# medulla_2026-05-01.net
KiCad netlist of a schematic drawn in EasyEDA Pro
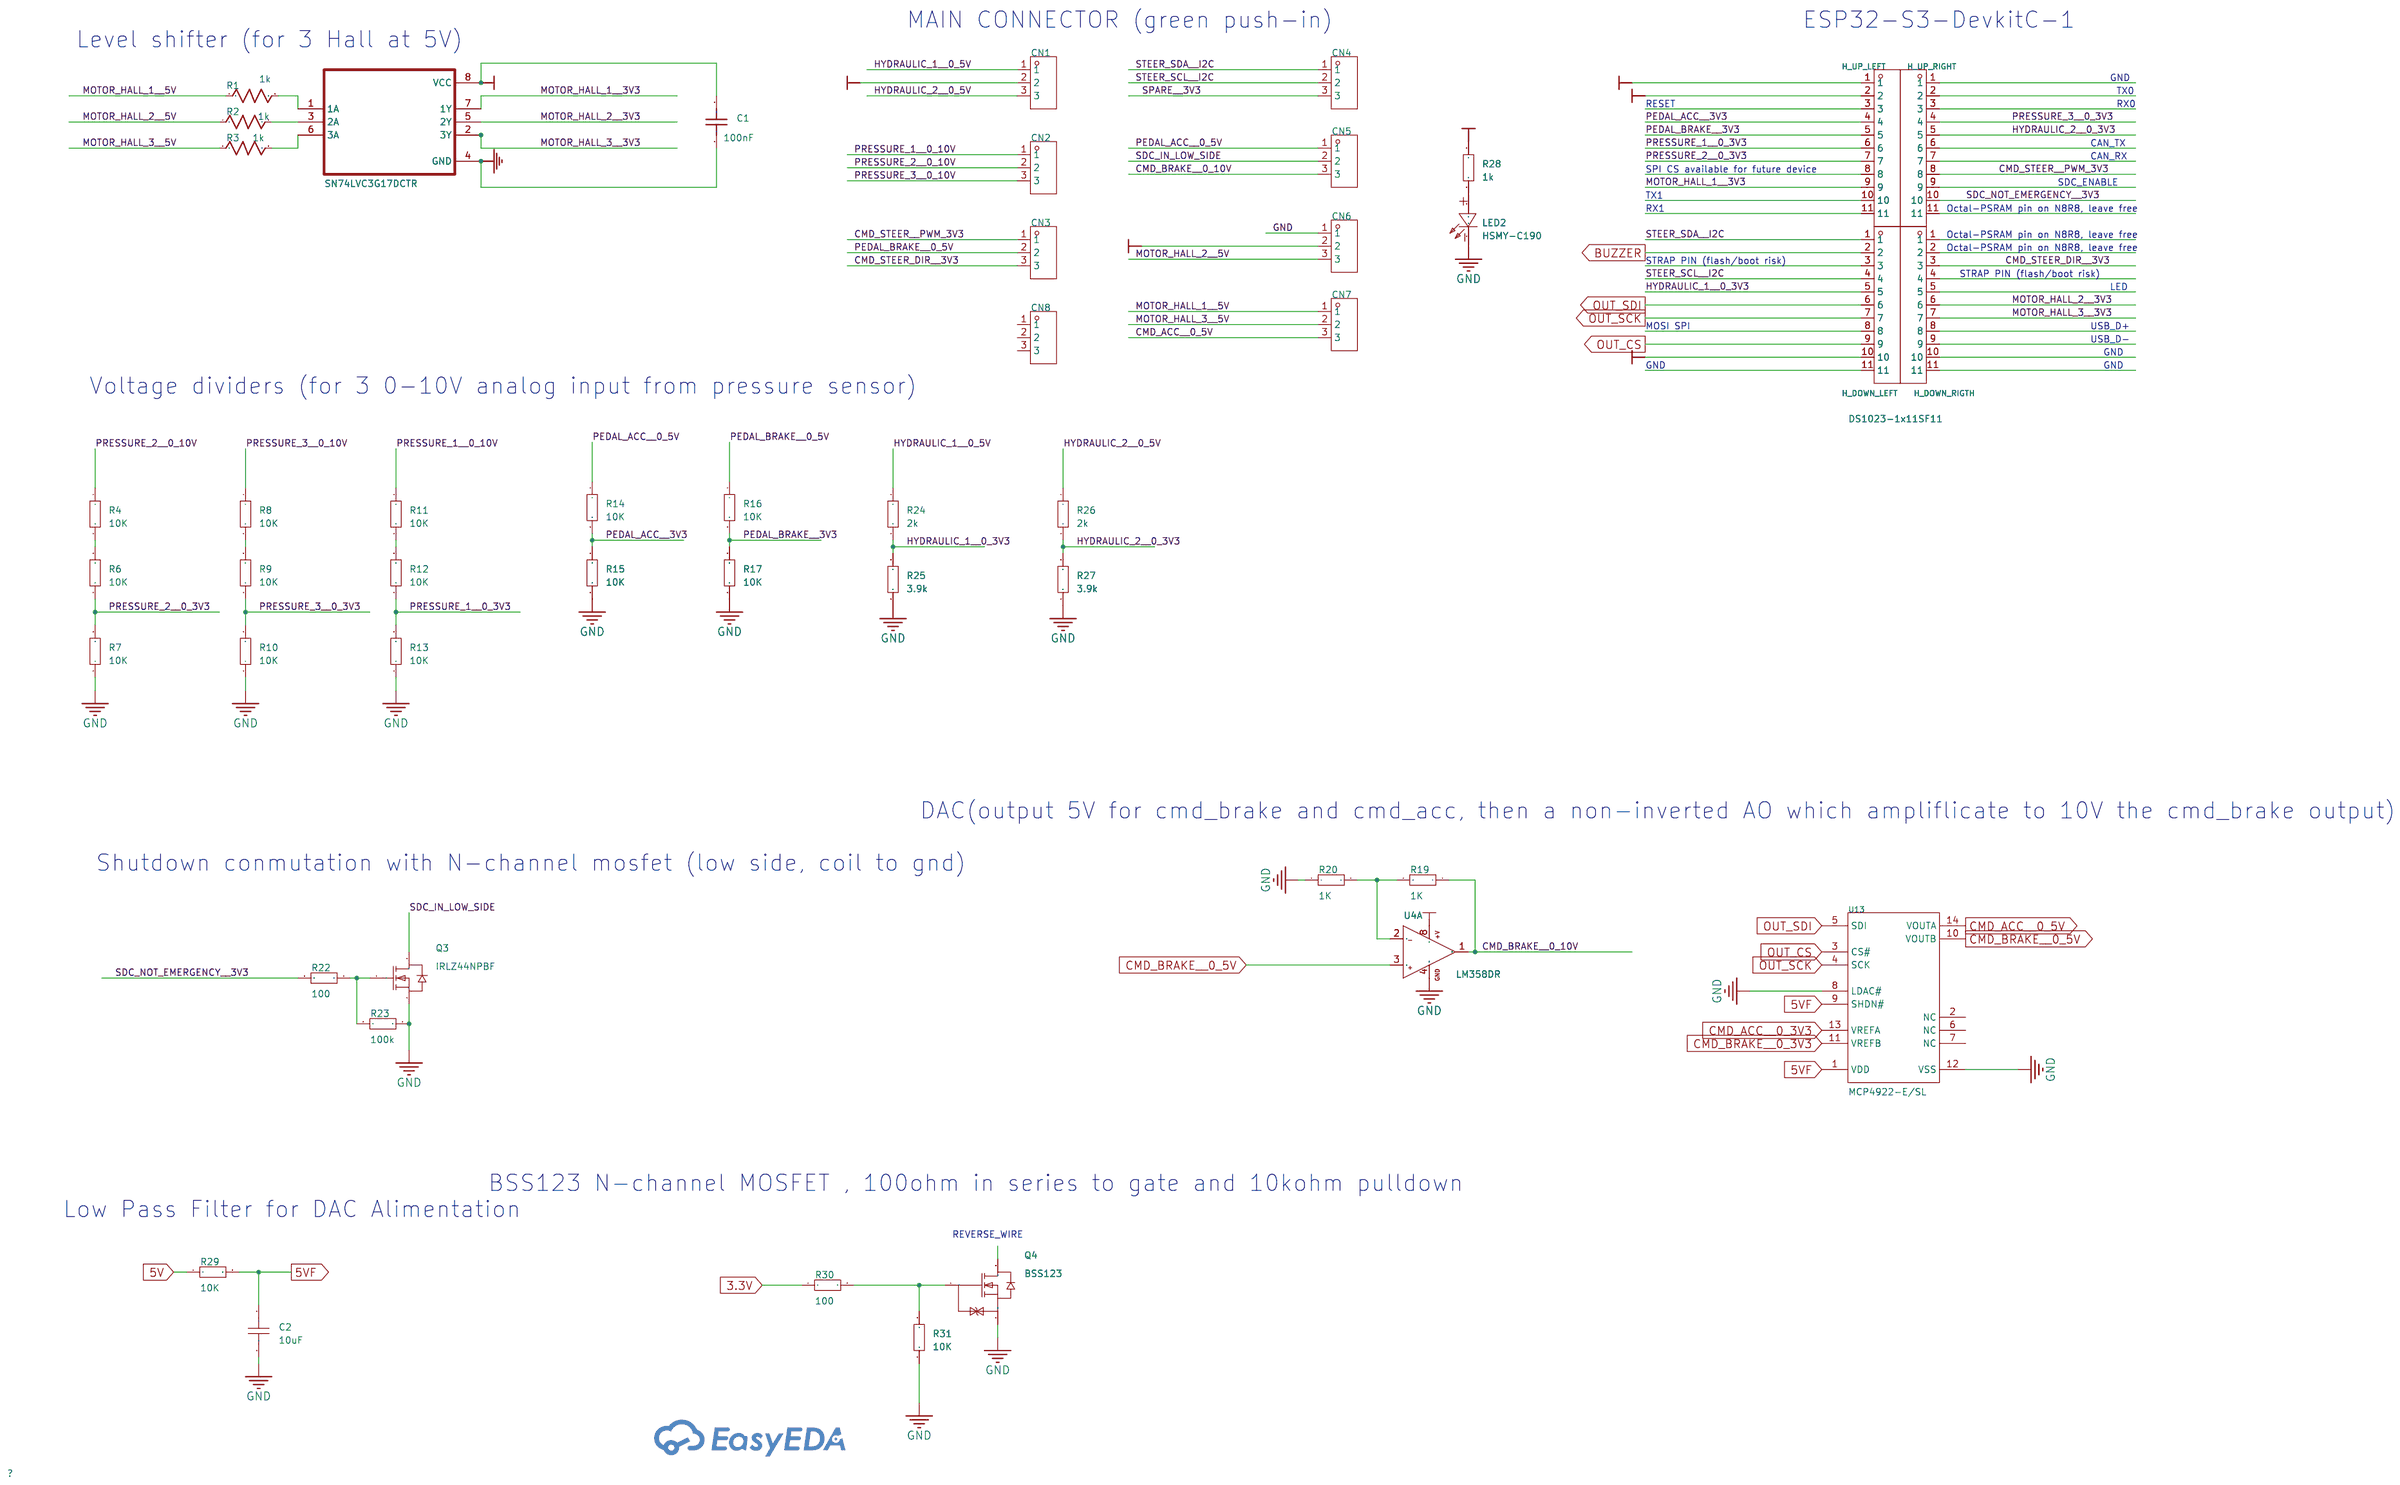
[diagram p0: schematic sheet]

(export (version "E")
  (design (tool "Eeschema 10.0.6"))
  (components
    (comp (ref "C1")
      (value "100nF")
      (footprint "easyedapro:C0603")
      (fields (field (name "Contributor") "LCEDA_Lib"))
      (libsource (lib "easyedapro") (part "100nF"))
    )
    (comp (ref "C2")
      (value "10uF")
      (footprint "easyedapro:C0603")
      (libsource (lib "easyedapro") (part "CAP"))
    )
    (comp (ref "CN1")
      (value "1990012")
      (footprint "easyedapro:CONN-TH_3P-P2.50-S5.00_1990012")
      (libsource (lib "easyedapro") (part "1990012"))
    )
    (comp (ref "CN2")
      (value "1990012")
      (footprint "easyedapro:CONN-TH_3P-P2.50-S5.00_1990012")
      (libsource (lib "easyedapro") (part "1990012"))
    )
    (comp (ref "CN3")
      (value "1990012")
      (footprint "easyedapro:CONN-TH_3P-P2.50-S5.00_1990012")
      (libsource (lib "easyedapro") (part "1990012"))
    )
    (comp (ref "CN4")
      (value "1990012")
      (footprint "easyedapro:CONN-TH_3P-P2.50-S5.00_1990012")
      (libsource (lib "easyedapro") (part "1990012"))
    )
    (comp (ref "CN5")
      (value "1990012")
      (footprint "easyedapro:CONN-TH_3P-P2.50-S5.00_1990012")
      (libsource (lib "easyedapro") (part "1990012"))
    )
    (comp (ref "CN6")
      (value "1990012")
      (footprint "easyedapro:CONN-TH_3P-P2.50-S5.00_1990012")
      (libsource (lib "easyedapro") (part "1990012"))
    )
    (comp (ref "CN7")
      (value "1990012")
      (footprint "easyedapro:CONN-TH_3P-P2.50-S5.00_1990012")
      (libsource (lib "easyedapro") (part "1990012"))
    )
    (comp (ref "CN8")
      (value "1990012")
      (footprint "easyedapro:CONN-TH_3P-P2.50-S5.00_1990012")
      (libsource (lib "easyedapro") (part "1990012"))
    )
    (comp (ref "H_DOWN_LEFT")
      (value "DS1023-1x11SF11")
      (footprint "easyedapro:HDR-TH_11P-P2.54-V-F")
      (fields (field (name "Manufacturer") "CONNFLY"))
      (libsource (lib "easyedapro") (part "DS1023-1X11SF11"))
    )
    (comp (ref "H_DOWN_RIGTH")
      (value "DS1023-1x11SF11")
      (footprint "easyedapro:HDR-TH_11P-P2.54-V-F")
      (fields (field (name "Manufacturer") "CONNFLY"))
      (libsource (lib "easyedapro") (part "DS1023-1X11SF11"))
    )
    (comp (ref "H_UP_LEFT")
      (value "DS1023-1x11SF11")
      (footprint "easyedapro:HDR-TH_11P-P2.54-V-F")
      (fields (field (name "Manufacturer") "CONNFLY"))
      (libsource (lib "easyedapro") (part "DS1023-1X11SF11"))
    )
    (comp (ref "H_UP_RIGHT")
      (value "DS1023-1x11SF11")
      (footprint "easyedapro:HDR-TH_11P-P2.54-V-F")
      (fields (field (name "Manufacturer") "CONNFLY"))
      (libsource (lib "easyedapro") (part "DS1023-1X11SF11"))
    )
    (comp (ref "LED2")
      (value "HSMY-C190")
      (footprint "easyedapro:LED-SMD_L1.6-W0.8-RD-YELLOW")
      (fields (field (name "Manufacturer") "Broadcom(博通)"))
      (libsource (lib "easyedapro") (part "HSMY-C190"))
    )
    (comp (ref "Q3")
      (value "IRLZ44NPBF")
      (footprint "easyedapro:TO-220-3_L10.0-W4.5-P2.54-T")
      (fields (field (name "Manufacturer") "Infineon(英飞凌)"))
      (libsource (lib "easyedapro") (part "IRLZ44NPBF"))
    )
    (comp (ref "Q4")
      (value "BSS123")
      (footprint "easyedapro:SOT-23_L2.9-W1.3-P1.90-LS2.4-BR")
      (fields (field (name "Manufacturer") "HXY MOSFET(华轩阳电子)"))
      (libsource (lib "easyedapro") (part "BSS123_C5184436"))
    )
    (comp (ref "R1")
      (value "1k")
      (footprint "easyedapro:R0603")
      (fields (field (name "Contributor") "LCEDA_Lib"))
      (libsource (lib "easyedapro") (part "1k"))
    )
    (comp (ref "R2")
      (value "1k")
      (footprint "easyedapro:R0603")
      (fields (field (name "Contributor") "LCEDA_Lib"))
      (libsource (lib "easyedapro") (part "1k"))
    )
    (comp (ref "R3")
      (value "1k")
      (footprint "easyedapro:R0603")
      (fields (field (name "Contributor") "LCEDA_Lib"))
      (libsource (lib "easyedapro") (part "1k"))
    )
    (comp (ref "R4") (value "10K") (footprint "easyedapro:R0603") (libsource (lib "easyedapro") (part "Res")))
    (comp (ref "R6") (value "10K") (footprint "easyedapro:R0603") (libsource (lib "easyedapro") (part "Res")))
    (comp (ref "R7") (value "10K") (footprint "easyedapro:R0603") (libsource (lib "easyedapro") (part "Res")))
    (comp (ref "R8") (value "10K") (footprint "easyedapro:R0603") (libsource (lib "easyedapro") (part "Res")))
    (comp (ref "R9") (value "10K") (footprint "easyedapro:R0603") (libsource (lib "easyedapro") (part "Res")))
    (comp (ref "R10")
      (value "10K")
      (footprint "easyedapro:R0603")
      (libsource (lib "easyedapro") (part "Res"))
    )
    (comp (ref "R11")
      (value "10K")
      (footprint "easyedapro:R0603")
      (libsource (lib "easyedapro") (part "Res"))
    )
    (comp (ref "R12")
      (value "10K")
      (footprint "easyedapro:R0603")
      (libsource (lib "easyedapro") (part "Res"))
    )
    (comp (ref "R13")
      (value "10K")
      (footprint "easyedapro:R0603")
      (libsource (lib "easyedapro") (part "Res"))
    )
    (comp (ref "R14")
      (value "10K")
      (footprint "easyedapro:R0603")
      (libsource (lib "easyedapro") (part "Res"))
    )
    (comp (ref "R15")
      (value "10K")
      (footprint "easyedapro:R0603")
      (libsource (lib "easyedapro") (part "Res"))
    )
    (comp (ref "R16")
      (value "10K")
      (footprint "easyedapro:R0603")
      (libsource (lib "easyedapro") (part "Res"))
    )
    (comp (ref "R17")
      (value "10K")
      (footprint "easyedapro:R0603")
      (libsource (lib "easyedapro") (part "Res"))
    )
    (comp (ref "R19") (value "1K") (footprint "easyedapro:R0603") (libsource (lib "easyedapro") (part "Res")))
    (comp (ref "R20") (value "1K") (footprint "easyedapro:R0603") (libsource (lib "easyedapro") (part "Res")))
    (comp (ref "R22")
      (value "100")
      (footprint "easyedapro:R0603")
      (libsource (lib "easyedapro") (part "Res"))
    )
    (comp (ref "R23")
      (value "100k")
      (footprint "easyedapro:R0603")
      (libsource (lib "easyedapro") (part "Res"))
    )
    (comp (ref "R24") (value "2k") (footprint "easyedapro:R0603") (libsource (lib "easyedapro") (part "Res")))
    (comp (ref "R25")
      (value "3.9k")
      (footprint "easyedapro:R0603")
      (libsource (lib "easyedapro") (part "Res"))
    )
    (comp (ref "R26") (value "2k") (footprint "easyedapro:R0603") (libsource (lib "easyedapro") (part "Res")))
    (comp (ref "R27")
      (value "3.9k")
      (footprint "easyedapro:R0603")
      (libsource (lib "easyedapro") (part "Res"))
    )
    (comp (ref "R28") (value "1k") (footprint "easyedapro:R0603") (libsource (lib "easyedapro") (part "Res")))
    (comp (ref "R29")
      (value "10K")
      (footprint "easyedapro:R0603")
      (libsource (lib "easyedapro") (part "Res"))
    )
    (comp (ref "R30")
      (value "100")
      (footprint "easyedapro:R0603")
      (libsource (lib "easyedapro") (part "Res"))
    )
    (comp (ref "R31")
      (value "10K")
      (footprint "easyedapro:R0603")
      (libsource (lib "easyedapro") (part "Res"))
    )
    (comp (ref "U4")
      (value "LM358DR")
      (footprint "easyedapro:SOIC-8_L5.0-W4.0-P1.27-LS6.0-BL")
      (fields (field (name "Manufacturer") "TI(德州仪器)"))
      (libsource (lib "easyedapro") (part "LM358DR"))
    )
    (comp (ref "U5")
      (value "SN74LVC3G17DCTR")
      (footprint "easyedapro:SOP65P400X130-8N")
      (libsource (lib "easyedapro") (part "SN74LVC3G17DCTR"))
    )
    (comp (ref "U13")
      (value "MCP4922-E/SL")
      (footprint "easyedapro:SOIC-14_L8.7-W3.9-P1.27-LS6.0-BL")
      (fields (field (name "Manufacturer") "MICROCHIP(美国微芯)"))
      (libsource (lib "easyedapro") (part "MCP4922-E/SL"))
    )
  )
  (nets
    (net (code "1") (name "/CMD_BRAKE__0_10V") (class "Default")
      (node (ref "CN5") (pin "3") (pinfunction "3_3") (pintype "unspecified"))
      (node (ref "R19") (pin "1") (pinfunction "1_1") (pintype "input"))
      (node (ref "U4") (pin "1") (pinfunction "OUT1_1") (pintype "output"))
    )
    (net (code "2") (name "/CMD_STEER_DIR__3V3") (class "Default")
      (node (ref "CN3") (pin "3") (pinfunction "3_3") (pintype "unspecified"))
      (node (ref "H_DOWN_RIGTH") (pin "3") (pinfunction "3_3") (pintype "input"))
    )
    (net (code "3") (name "/CMD_STEER__PWM_3V3") (class "Default")
      (node (ref "CN3") (pin "1") (pinfunction "1_1") (pintype "unspecified"))
      (node (ref "H_UP_RIGHT") (pin "8") (pinfunction "8_8") (pintype "input"))
    )
    (net (code "4") (name "/HYDRAULIC_1__0_3V3") (class "Default")
      (node (ref "H_DOWN_LEFT") (pin "5") (pinfunction "5_5") (pintype "input"))
      (node (ref "R24") (pin "2") (pinfunction "2_2") (pintype "input"))
      (node (ref "R25") (pin "2") (pinfunction "2_2") (pintype "input"))
    )
    (net (code "5") (name "/HYDRAULIC_1__0_5V") (class "Default")
      (node (ref "CN1") (pin "1") (pinfunction "1_1") (pintype "unspecified"))
      (node (ref "R24") (pin "1") (pinfunction "1_1") (pintype "input"))
    )
    (net (code "6") (name "/HYDRAULIC_2__0_3V3") (class "Default")
      (node (ref "H_UP_RIGHT") (pin "5") (pinfunction "5_5") (pintype "input"))
      (node (ref "R26") (pin "2") (pinfunction "2_2") (pintype "input"))
      (node (ref "R27") (pin "2") (pinfunction "2_2") (pintype "input"))
    )
    (net (code "7") (name "/HYDRAULIC_2__0_5V") (class "Default")
      (node (ref "CN1") (pin "3") (pinfunction "3_3") (pintype "unspecified"))
      (node (ref "R26") (pin "1") (pinfunction "1_1") (pintype "input"))
    )
    (net (code "8") (name "/MOTOR_HALL_1__3V3") (class "Default")
      (node (ref "H_UP_LEFT") (pin "9") (pinfunction "9_9") (pintype "input"))
      (node (ref "U5") (pin "7") (pinfunction "1Y_7") (pintype "output"))
    )
    (net (code "9") (name "/MOTOR_HALL_1__5V") (class "Default")
      (node (ref "CN7") (pin "1") (pinfunction "1_1") (pintype "unspecified"))
      (node (ref "R1") (pin "1") (pinfunction "1_1") (pintype "unspecified"))
    )
    (net (code "10") (name "/MOTOR_HALL_2__3V3") (class "Default")
      (node (ref "H_DOWN_RIGTH") (pin "6") (pinfunction "6_6") (pintype "input"))
      (node (ref "U5") (pin "5") (pinfunction "2Y_5") (pintype "output"))
    )
    (net (code "11") (name "/MOTOR_HALL_2__5V") (class "Default")
      (node (ref "CN6") (pin "3") (pinfunction "3_3") (pintype "unspecified"))
      (node (ref "R2") (pin "1") (pinfunction "1_1") (pintype "unspecified"))
    )
    (net (code "12") (name "/MOTOR_HALL_3__3V3") (class "Default")
      (node (ref "H_DOWN_RIGTH") (pin "7") (pinfunction "7_7") (pintype "input"))
      (node (ref "U5") (pin "2") (pinfunction "3Y_2") (pintype "output"))
    )
    (net (code "13") (name "/MOTOR_HALL_3__5V") (class "Default")
      (node (ref "CN7") (pin "2") (pinfunction "2_2") (pintype "unspecified"))
      (node (ref "R3") (pin "1") (pinfunction "1_1") (pintype "unspecified"))
    )
    (net (code "14") (name "/PEDAL_ACC__0_5V") (class "Default")
      (node (ref "CN5") (pin "1") (pinfunction "1_1") (pintype "unspecified"))
      (node (ref "R14") (pin "1") (pinfunction "1_1") (pintype "input"))
    )
    (net (code "15") (name "/PEDAL_ACC__3V3") (class "Default")
      (node (ref "H_UP_LEFT") (pin "4") (pinfunction "4_4") (pintype "input"))
      (node (ref "R14") (pin "2") (pinfunction "2_2") (pintype "input"))
      (node (ref "R15") (pin "2") (pinfunction "2_2") (pintype "input"))
    )
    (net (code "16") (name "/PEDAL_BRAKE__0_5V") (class "Default")
      (node (ref "CN3") (pin "2") (pinfunction "2_2") (pintype "unspecified"))
      (node (ref "R16") (pin "1") (pinfunction "1_1") (pintype "input"))
    )
    (net (code "17") (name "/PEDAL_BRAKE__3V3") (class "Default")
      (node (ref "H_UP_LEFT") (pin "5") (pinfunction "5_5") (pintype "input"))
      (node (ref "R16") (pin "2") (pinfunction "2_2") (pintype "input"))
      (node (ref "R17") (pin "2") (pinfunction "2_2") (pintype "input"))
    )
    (net (code "18") (name "/PRESSURE_1__0_3V3") (class "Default")
      (node (ref "H_UP_LEFT") (pin "6") (pinfunction "6_6") (pintype "input"))
      (node (ref "R12") (pin "1") (pinfunction "1_1") (pintype "input"))
      (node (ref "R13") (pin "2") (pinfunction "2_2") (pintype "input"))
    )
    (net (code "19") (name "/PRESSURE_1__0_10V") (class "Default")
      (node (ref "CN2") (pin "1") (pinfunction "1_1") (pintype "unspecified"))
      (node (ref "R11") (pin "1") (pinfunction "1_1") (pintype "input"))
    )
    (net (code "20") (name "/PRESSURE_2__0_3V3") (class "Default")
      (node (ref "H_UP_LEFT") (pin "7") (pinfunction "7_7") (pintype "input"))
      (node (ref "R6") (pin "1") (pinfunction "1_1") (pintype "input"))
      (node (ref "R7") (pin "2") (pinfunction "2_2") (pintype "input"))
    )
    (net (code "21") (name "/PRESSURE_2__0_10V") (class "Default")
      (node (ref "CN2") (pin "2") (pinfunction "2_2") (pintype "unspecified"))
      (node (ref "R4") (pin "1") (pinfunction "1_1") (pintype "input"))
    )
    (net (code "22") (name "/PRESSURE_3__0_3V3") (class "Default")
      (node (ref "H_UP_RIGHT") (pin "4") (pinfunction "4_4") (pintype "input"))
      (node (ref "R10") (pin "2") (pinfunction "2_2") (pintype "input"))
      (node (ref "R9") (pin "1") (pinfunction "1_1") (pintype "input"))
    )
    (net (code "23") (name "/PRESSURE_3__0_10V") (class "Default")
      (node (ref "CN2") (pin "3") (pinfunction "3_3") (pintype "unspecified"))
      (node (ref "R8") (pin "1") (pinfunction "1_1") (pintype "input"))
    )
    (net (code "24") (name "/SDC_IN_LOW_SIDE") (class "Default")
      (node (ref "CN5") (pin "2") (pinfunction "2_2") (pintype "unspecified"))
      (node (ref "Q3") (pin "2") (pinfunction "D_2") (pintype "unspecified"))
    )
    (net (code "25") (name "/SDC_NOT_EMERGENCY__3V3") (class "Default")
      (node (ref "H_UP_RIGHT") (pin "10") (pinfunction "10_10") (pintype "input"))
      (node (ref "R22") (pin "2") (pinfunction "2_2") (pintype "input"))
    )
    (net (code "26") (name "/SPARE__3V3") (class "Default")
      (node (ref "CN4") (pin "3") (pinfunction "3_3") (pintype "unspecified"))
    )
    (net (code "27") (name "/STEER_SCL__I2C") (class "Default")
      (node (ref "CN4") (pin "2") (pinfunction "2_2") (pintype "unspecified"))
      (node (ref "H_DOWN_LEFT") (pin "4") (pinfunction "4_4") (pintype "input"))
    )
    (net (code "28") (name "/STEER_SDA__I2C") (class "Default")
      (node (ref "CN4") (pin "1") (pinfunction "1_1") (pintype "unspecified"))
      (node (ref "H_DOWN_LEFT") (pin "1") (pinfunction "1_1") (pintype "input"))
    )
    (net (code "29") (name "3.3V") (class "Default")
      (node (ref "R30") (pin "1") (pinfunction "1_1") (pintype "input"))
    )
    (net (code "30") (name "3V3") (class "Default")
      (node (ref "C1") (pin "2") (pinfunction "2_2") (pintype "unspecified"))
      (node (ref "CN1") (pin "2") (pinfunction "2_2") (pintype "unspecified"))
      (node (ref "H_UP_LEFT") (pin "1") (pinfunction "1_1") (pintype "input"))
      (node (ref "H_UP_LEFT") (pin "2") (pinfunction "2_2") (pintype "input"))
      (node (ref "R28") (pin "1") (pinfunction "1_1") (pintype "input"))
      (node (ref "U5") (pin "8") (pinfunction "VCC_8") (pintype "unspecified"))
    )
    (net (code "31") (name "5V") (class "Default")
      (node (ref "H_DOWN_LEFT") (pin "10") (pinfunction "10_10") (pintype "input"))
      (node (ref "R29") (pin "1") (pinfunction "1_1") (pintype "input"))
    )
    (net (code "32") (name "5VF") (class "Default")
      (node (ref "C2") (pin "1") (pinfunction "1_1") (pintype "input"))
      (node (ref "R29") (pin "2") (pinfunction "2_2") (pintype "input"))
      (node (ref "U13") (pin "1") (pinfunction "VDD_1") (pintype "input"))
      (node (ref "U13") (pin "9") (pinfunction "SHDN#_9") (pintype "input"))
    )
    (net (code "33") (name "12V") (class "Default")
      (node (ref "CN6") (pin "2") (pinfunction "2_2") (pintype "unspecified"))
      (node (ref "U4") (pin "8") (pinfunction "+V_8") (pintype "unspecified"))
    )
    (net (code "34") (name "BUZZER") (class "Default")
      (node (ref "H_DOWN_LEFT") (pin "2") (pinfunction "2_2") (pintype "input"))
    )
    (net (code "35") (name "CMD_ACC__0_3V3") (class "Default")
      (node (ref "U13") (pin "13") (pinfunction "VREFA_13") (pintype "input"))
    )
    (net (code "36") (name "CMD_ACC__0_5V") (class "Default")
      (node (ref "CN7") (pin "3") (pinfunction "3_3") (pintype "unspecified"))
      (node (ref "U13") (pin "14") (pinfunction "VOUTA_14") (pintype "output"))
    )
    (net (code "37") (name "CMD_BRAKE__0_3V3") (class "Default")
      (node (ref "U13") (pin "11") (pinfunction "VREFB_11") (pintype "input"))
    )
    (net (code "38") (name "CMD_BRAKE__0_5V") (class "Default")
      (node (ref "U13") (pin "10") (pinfunction "VOUTB_10") (pintype "output"))
      (node (ref "U4") (pin "3") (pinfunction "+IN1_3") (pintype "input"))
    )
    (net (code "39") (name "GND") (class "Default")
      (node (ref "C1") (pin "1") (pinfunction "1_1") (pintype "unspecified"))
      (node (ref "C2") (pin "2") (pinfunction "2_2") (pintype "input"))
      (node (ref "CN6") (pin "1") (pinfunction "1_1") (pintype "unspecified"))
      (node (ref "LED2") (pin "1") (pinfunction "A_1") (pintype "unspecified"))
      (node (ref "Q3") (pin "3") (pinfunction "S_3") (pintype "unspecified"))
      (node (ref "Q4") (pin "2") (pinfunction "S_2") (pintype "unspecified"))
      (node (ref "R10") (pin "1") (pinfunction "1_1") (pintype "input"))
      (node (ref "R13") (pin "1") (pinfunction "1_1") (pintype "input"))
      (node (ref "R15") (pin "1") (pinfunction "1_1") (pintype "input"))
      (node (ref "R17") (pin "1") (pinfunction "1_1") (pintype "input"))
      (node (ref "R20") (pin "1") (pinfunction "1_1") (pintype "input"))
      (node (ref "R23") (pin "1") (pinfunction "1_1") (pintype "input"))
      (node (ref "R25") (pin "1") (pinfunction "1_1") (pintype "input"))
      (node (ref "R27") (pin "1") (pinfunction "1_1") (pintype "input"))
      (node (ref "R31") (pin "1") (pinfunction "1_1") (pintype "input"))
      (node (ref "R7") (pin "1") (pinfunction "1_1") (pintype "input"))
      (node (ref "U13") (pin "12") (pinfunction "VSS_12") (pintype "input"))
      (node (ref "U13") (pin "8") (pinfunction "LDAC#_8") (pintype "input"))
      (node (ref "U4") (pin "4") (pinfunction "GND_4") (pintype "unspecified"))
      (node (ref "U5") (pin "4") (pinfunction "GND_4") (pintype "unspecified"))
    )
    (net (code "40") (name "Net-(LED2-C)") (class "Default")
      (node (ref "LED2") (pin "2") (pinfunction "C_2") (pintype "unspecified"))
      (node (ref "R28") (pin "2") (pinfunction "2_2") (pintype "input"))
    )
    (net (code "41") (name "Net-(Q3-G)") (class "Default")
      (node (ref "Q3") (pin "1") (pinfunction "G_1") (pintype "unspecified"))
      (node (ref "R22") (pin "1") (pinfunction "1_1") (pintype "input"))
      (node (ref "R23") (pin "2") (pinfunction "2_2") (pintype "input"))
    )
    (net (code "42") (name "Net-(Q4-G)") (class "Default")
      (node (ref "Q4") (pin "1") (pinfunction "G_1") (pintype "unspecified"))
      (node (ref "R30") (pin "2") (pinfunction "2_2") (pintype "input"))
      (node (ref "R31") (pin "2") (pinfunction "2_2") (pintype "input"))
    )
    (net (code "43") (name "Net-(R4-Pad2)") (class "Default")
      (node (ref "R4") (pin "2") (pinfunction "2_2") (pintype "input"))
      (node (ref "R6") (pin "2") (pinfunction "2_2") (pintype "input"))
    )
    (net (code "44") (name "Net-(R8-Pad2)") (class "Default")
      (node (ref "R8") (pin "2") (pinfunction "2_2") (pintype "input"))
      (node (ref "R9") (pin "2") (pinfunction "2_2") (pintype "input"))
    )
    (net (code "45") (name "Net-(R11-Pad2)") (class "Default")
      (node (ref "R11") (pin "2") (pinfunction "2_2") (pintype "input"))
      (node (ref "R12") (pin "2") (pinfunction "2_2") (pintype "input"))
    )
    (net (code "46") (name "Net-(U4A--IN1)") (class "Default")
      (node (ref "R19") (pin "2") (pinfunction "2_2") (pintype "input"))
      (node (ref "R20") (pin "2") (pinfunction "2_2") (pintype "input"))
      (node (ref "U4") (pin "2") (pinfunction "-IN1_2") (pintype "input"))
    )
    (net (code "47") (name "Net-(U5-1A)") (class "Default")
      (node (ref "R1") (pin "2") (pinfunction "2_2") (pintype "unspecified"))
      (node (ref "U5") (pin "1") (pinfunction "1A_1") (pintype "input"))
    )
    (net (code "48") (name "Net-(U5-2A)") (class "Default")
      (node (ref "R2") (pin "2") (pinfunction "2_2") (pintype "unspecified"))
      (node (ref "U5") (pin "3") (pinfunction "2A_3") (pintype "input"))
    )
    (net (code "49") (name "Net-(U5-3A)") (class "Default")
      (node (ref "R3") (pin "2") (pinfunction "2_2") (pintype "unspecified"))
      (node (ref "U5") (pin "6") (pinfunction "3A_6") (pintype "input"))
    )
    (net (code "50") (name "OUT_CS") (class "Default")
      (node (ref "H_DOWN_LEFT") (pin "9") (pinfunction "9_9") (pintype "input"))
      (node (ref "U13") (pin "3") (pinfunction "CS#_3") (pintype "input"))
    )
    (net (code "51") (name "OUT_SCK") (class "Default")
      (node (ref "H_DOWN_LEFT") (pin "7") (pinfunction "7_7") (pintype "input"))
      (node (ref "U13") (pin "4") (pinfunction "SCK_4") (pintype "input"))
    )
    (net (code "52") (name "OUT_SDI") (class "Default")
      (node (ref "H_DOWN_LEFT") (pin "6") (pinfunction "6_6") (pintype "input"))
      (node (ref "U13") (pin "5") (pinfunction "SDI_5") (pintype "input"))
    )
    (net (code "53") (name "unconnected-(CN8-Pad1)") (class "Default")
      (node (ref "CN8") (pin "1") (pinfunction "1_1") (pintype "unspecified"))
    )
    (net (code "54") (name "unconnected-(CN8-Pad2)") (class "Default")
      (node (ref "CN8") (pin "2") (pinfunction "2_2") (pintype "unspecified"))
    )
    (net (code "55") (name "unconnected-(CN8-Pad3)") (class "Default")
      (node (ref "CN8") (pin "3") (pinfunction "3_3") (pintype "unspecified"))
    )
    (net (code "56") (name "unconnected-(H_DOWN_LEFT-Pad3)") (class "Default")
      (node (ref "H_DOWN_LEFT") (pin "3") (pinfunction "3_3") (pintype "input"))
    )
    (net (code "57") (name "unconnected-(H_DOWN_LEFT-Pad8)") (class "Default")
      (node (ref "H_DOWN_LEFT") (pin "8") (pinfunction "8_8") (pintype "input"))
    )
    (net (code "58") (name "unconnected-(H_DOWN_LEFT-Pad11)") (class "Default")
      (node (ref "H_DOWN_LEFT") (pin "11") (pinfunction "11_11") (pintype "input"))
    )
    (net (code "59") (name "unconnected-(H_DOWN_RIGTH-Pad1)") (class "Default")
      (node (ref "H_DOWN_RIGTH") (pin "1") (pinfunction "1_1") (pintype "input"))
    )
    (net (code "60") (name "unconnected-(H_DOWN_RIGTH-Pad2)") (class "Default")
      (node (ref "H_DOWN_RIGTH") (pin "2") (pinfunction "2_2") (pintype "input"))
    )
    (net (code "61") (name "unconnected-(H_DOWN_RIGTH-Pad4)") (class "Default")
      (node (ref "H_DOWN_RIGTH") (pin "4") (pinfunction "4_4") (pintype "input"))
    )
    (net (code "62") (name "unconnected-(H_DOWN_RIGTH-Pad5)") (class "Default")
      (node (ref "H_DOWN_RIGTH") (pin "5") (pinfunction "5_5") (pintype "input"))
    )
    (net (code "63") (name "unconnected-(H_DOWN_RIGTH-Pad8)") (class "Default")
      (node (ref "H_DOWN_RIGTH") (pin "8") (pinfunction "8_8") (pintype "input"))
    )
    (net (code "64") (name "unconnected-(H_DOWN_RIGTH-Pad9)") (class "Default")
      (node (ref "H_DOWN_RIGTH") (pin "9") (pinfunction "9_9") (pintype "input"))
    )
    (net (code "65") (name "unconnected-(H_DOWN_RIGTH-Pad10)") (class "Default")
      (node (ref "H_DOWN_RIGTH") (pin "10") (pinfunction "10_10") (pintype "input"))
    )
    (net (code "66") (name "unconnected-(H_DOWN_RIGTH-Pad11)") (class "Default")
      (node (ref "H_DOWN_RIGTH") (pin "11") (pinfunction "11_11") (pintype "input"))
    )
    (net (code "67") (name "unconnected-(H_UP_LEFT-Pad3)") (class "Default")
      (node (ref "H_UP_LEFT") (pin "3") (pinfunction "3_3") (pintype "input"))
    )
    (net (code "68") (name "unconnected-(H_UP_LEFT-Pad8)") (class "Default")
      (node (ref "H_UP_LEFT") (pin "8") (pinfunction "8_8") (pintype "input"))
    )
    (net (code "69") (name "unconnected-(H_UP_LEFT-Pad10)") (class "Default")
      (node (ref "H_UP_LEFT") (pin "10") (pinfunction "10_10") (pintype "input"))
    )
    (net (code "70") (name "unconnected-(H_UP_LEFT-Pad11)") (class "Default")
      (node (ref "H_UP_LEFT") (pin "11") (pinfunction "11_11") (pintype "input"))
    )
    (net (code "71") (name "unconnected-(H_UP_RIGHT-Pad1)") (class "Default")
      (node (ref "H_UP_RIGHT") (pin "1") (pinfunction "1_1") (pintype "input"))
    )
    (net (code "72") (name "unconnected-(H_UP_RIGHT-Pad2)") (class "Default")
      (node (ref "H_UP_RIGHT") (pin "2") (pinfunction "2_2") (pintype "input"))
    )
    (net (code "73") (name "unconnected-(H_UP_RIGHT-Pad3)") (class "Default")
      (node (ref "H_UP_RIGHT") (pin "3") (pinfunction "3_3") (pintype "input"))
    )
    (net (code "74") (name "unconnected-(H_UP_RIGHT-Pad6)") (class "Default")
      (node (ref "H_UP_RIGHT") (pin "6") (pinfunction "6_6") (pintype "input"))
    )
    (net (code "75") (name "unconnected-(H_UP_RIGHT-Pad7)") (class "Default")
      (node (ref "H_UP_RIGHT") (pin "7") (pinfunction "7_7") (pintype "input"))
    )
    (net (code "76") (name "unconnected-(H_UP_RIGHT-Pad9)") (class "Default")
      (node (ref "H_UP_RIGHT") (pin "9") (pinfunction "9_9") (pintype "input"))
    )
    (net (code "77") (name "unconnected-(H_UP_RIGHT-Pad11)") (class "Default")
      (node (ref "H_UP_RIGHT") (pin "11") (pinfunction "11_11") (pintype "input"))
    )
    (net (code "78") (name "unconnected-(Q4-D-Pad3)") (class "Default")
      (node (ref "Q4") (pin "3") (pinfunction "D_3") (pintype "unspecified"))
    )
    (net (code "79") (name "unconnected-(U13-NC-Pad2)") (class "Default")
      (node (ref "U13") (pin "2") (pinfunction "NC_2") (pintype "input"))
    )
    (net (code "80") (name "unconnected-(U13-NC-Pad6)") (class "Default")
      (node (ref "U13") (pin "6") (pinfunction "NC_6") (pintype "input"))
    )
    (net (code "81") (name "unconnected-(U13-NC-Pad7)") (class "Default")
      (node (ref "U13") (pin "7") (pinfunction "NC_7") (pintype "input"))
    )
  )
)
